# tarocco.net
KiCad netlist of a schematic drawn in EAGLE
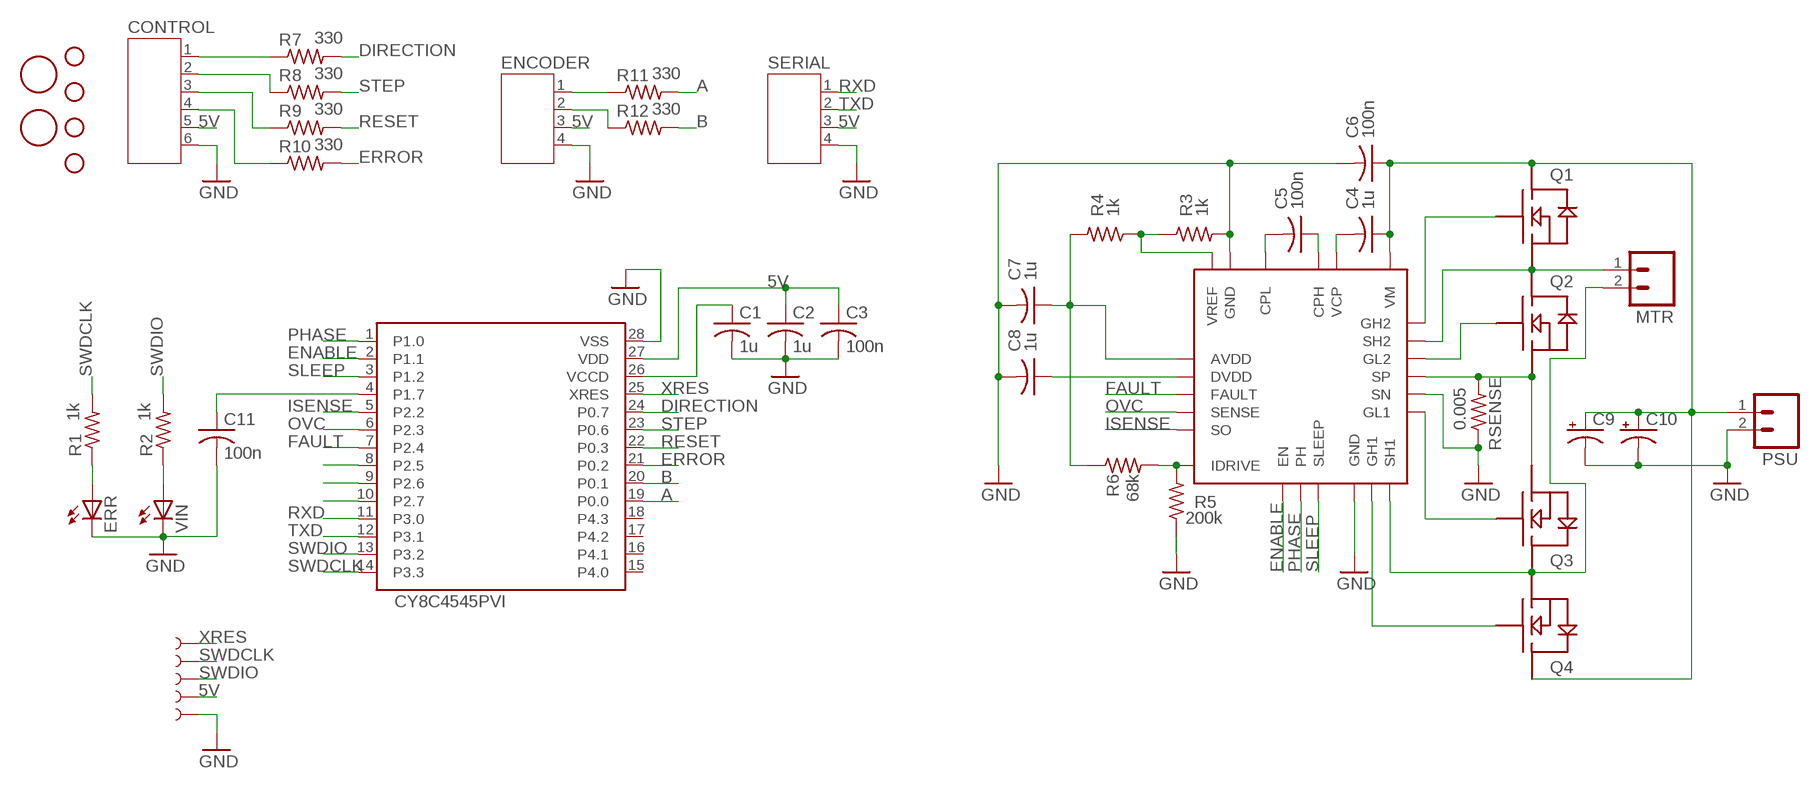
[diagram p0: schematic, sheet 1]

(export (version "E")
  (design (tool "Eeschema 10.0.6"))
  (components
    (comp (ref "8701")
      (value "DRV8701")
      (footprint "eagle-import:VQFN24")
      (libsource (lib "eagle-import") (part "DRV8701"))
    )
    (comp (ref "C1")
      (value "1u")
      (footprint "eagle-import:C0603")
      (libsource (lib "eagle-import") (part "C-USC0603"))
    )
    (comp (ref "C2")
      (value "1u")
      (footprint "eagle-import:C0603")
      (libsource (lib "eagle-import") (part "C-USC0603"))
    )
    (comp (ref "C3")
      (value "100n")
      (footprint "eagle-import:C0603")
      (libsource (lib "eagle-import") (part "C-USC0603"))
    )
    (comp (ref "C4")
      (value "1u")
      (footprint "eagle-import:C0603")
      (libsource (lib "eagle-import") (part "C-USC0603"))
    )
    (comp (ref "C5")
      (value "100n")
      (footprint "eagle-import:C0603")
      (libsource (lib "eagle-import") (part "C-USC0603"))
    )
    (comp (ref "C6")
      (value "100n")
      (footprint "eagle-import:C0603")
      (libsource (lib "eagle-import") (part "C-USC0603"))
    )
    (comp (ref "C7")
      (value "1u")
      (footprint "eagle-import:C0603")
      (libsource (lib "eagle-import") (part "C-USC0603"))
    )
    (comp (ref "C8")
      (value "1u")
      (footprint "eagle-import:C0603")
      (libsource (lib "eagle-import") (part "C-USC0603"))
    )
    (comp (ref "C9")
      (value "CPOL-USE3.5-8")
      (footprint "eagle-import:E3,5-8")
      (libsource (lib "eagle-import") (part "CPOL-USE3.5-8"))
    )
    (comp (ref "C10")
      (value "CPOL-USE3.5-8")
      (footprint "eagle-import:E3,5-8")
      (libsource (lib "eagle-import") (part "CPOL-USE3.5-8"))
    )
    (comp (ref "C11")
      (value "100n")
      (footprint "eagle-import:C0603")
      (libsource (lib "eagle-import") (part "C-USC0603"))
    )
    (comp (ref "CONTROL")
      (value "JST-PH6")
      (footprint "eagle-import:JST-PH6")
      (libsource (lib "eagle-import") (part "JST-PH6"))
    )
    (comp (ref "ENCODER")
      (value "JST-PH4")
      (footprint "eagle-import:JST-PH4")
      (libsource (lib "eagle-import") (part "JST-PH4"))
    )
    (comp (ref "ERR")
      (value "LEDCHIP-LED0603")
      (footprint "eagle-import:CHIP-LED0603")
      (libsource (lib "eagle-import") (part "LEDCHIP-LED0603"))
    )
    (comp (ref "IC1")
      (value "CY8C4545PVI")
      (footprint "eagle-import:SSOP28")
      (libsource (lib "eagle-import") (part "CY8C4545PVI"))
    )
    (comp (ref "MTR")
      (value "M023.5MM")
      (footprint "eagle-import:SCREWTERMINAL-3.5MM-2")
      (libsource (lib "eagle-import") (part "M023.5MM"))
    )
    (comp (ref "PSU")
      (value "M023.5MM")
      (footprint "eagle-import:SCREWTERMINAL-3.5MM-2")
      (libsource (lib "eagle-import") (part "M023.5MM"))
    )
    (comp (ref "Q1")
      (value "NEXFET_SINGLECSD18537NQ5A")
      (footprint "eagle-import:SON5X6")
      (libsource (lib "eagle-import") (part "NEXFET_SINGLECSD18537NQ5A"))
    )
    (comp (ref "Q2")
      (value "NEXFET_SINGLECSD18537NQ5A")
      (footprint "eagle-import:SON5X6")
      (libsource (lib "eagle-import") (part "NEXFET_SINGLECSD18537NQ5A"))
    )
    (comp (ref "Q3")
      (value "NEXFET_SINGLECSD18537NQ5A")
      (footprint "eagle-import:SON5X6")
      (libsource (lib "eagle-import") (part "NEXFET_SINGLECSD18537NQ5A"))
    )
    (comp (ref "Q4")
      (value "NEXFET_SINGLECSD18537NQ5A")
      (footprint "eagle-import:SON5X6")
      (libsource (lib "eagle-import") (part "NEXFET_SINGLECSD18537NQ5A"))
    )
    (comp (ref "R1")
      (value "1k")
      (footprint "eagle-import:R0603")
      (libsource (lib "eagle-import") (part "R-US_R0603"))
    )
    (comp (ref "R2")
      (value "1k")
      (footprint "eagle-import:R0603")
      (libsource (lib "eagle-import") (part "R-US_R0603"))
    )
    (comp (ref "R3")
      (value "1k")
      (footprint "eagle-import:R0603")
      (libsource (lib "eagle-import") (part "R-US_R0603"))
    )
    (comp (ref "R4")
      (value "1k")
      (footprint "eagle-import:R0603")
      (libsource (lib "eagle-import") (part "R-US_R0603"))
    )
    (comp (ref "R5")
      (value "200k")
      (footprint "eagle-import:R0603")
      (libsource (lib "eagle-import") (part "R-US_R0603"))
    )
    (comp (ref "R6")
      (value "68k")
      (footprint "eagle-import:R0603")
      (libsource (lib "eagle-import") (part "R-US_R0603"))
    )
    (comp (ref "R7")
      (value "330")
      (footprint "eagle-import:R0603")
      (libsource (lib "eagle-import") (part "R-US_R0603"))
    )
    (comp (ref "R8")
      (value "330")
      (footprint "eagle-import:R0603")
      (libsource (lib "eagle-import") (part "R-US_R0603"))
    )
    (comp (ref "R9")
      (value "330")
      (footprint "eagle-import:R0603")
      (libsource (lib "eagle-import") (part "R-US_R0603"))
    )
    (comp (ref "R10")
      (value "330")
      (footprint "eagle-import:R0603")
      (libsource (lib "eagle-import") (part "R-US_R0603"))
    )
    (comp (ref "R11")
      (value "330")
      (footprint "eagle-import:R0603")
      (libsource (lib "eagle-import") (part "R-US_R0603"))
    )
    (comp (ref "R12")
      (value "330")
      (footprint "eagle-import:R0603")
      (libsource (lib "eagle-import") (part "R-US_R0603"))
    )
    (comp (ref "RSENSE")
      (value "0.005")
      (footprint "eagle-import:R2512")
      (libsource (lib "eagle-import") (part "R-US_R2512"))
    )
    (comp (ref "SERIAL")
      (value "JST-PH4")
      (footprint "eagle-import:JST-PH4")
      (libsource (lib "eagle-import") (part "JST-PH4"))
    )
    (comp (ref "STANDOFF1")
      (value "STAND-OFF")
      (footprint "eagle-import:STAND-OFF")
      (libsource (lib "eagle-import") (part "STAND-OFF"))
    )
    (comp (ref "STANDOFF2")
      (value "STAND-OFF")
      (footprint "eagle-import:STAND-OFF")
      (libsource (lib "eagle-import") (part "STAND-OFF"))
    )
    (comp (ref "STANDOFF3")
      (value "STAND-OFF")
      (footprint "eagle-import:STAND-OFF")
      (libsource (lib "eagle-import") (part "STAND-OFF"))
    )
    (comp (ref "STANDOFF4")
      (value "STAND-OFF")
      (footprint "eagle-import:STAND-OFF")
      (libsource (lib "eagle-import") (part "STAND-OFF"))
    )
    (comp (ref "TP1")
      (value "TEST-POINT3X5")
      (footprint "eagle-import:PAD.03X.05")
      (libsource (lib "eagle-import") (part "TEST-POINT3X5"))
    )
    (comp (ref "TP2")
      (value "TEST-POINT3X5")
      (footprint "eagle-import:PAD.03X.05")
      (libsource (lib "eagle-import") (part "TEST-POINT3X5"))
    )
    (comp (ref "TP3")
      (value "TEST-POINT3X5")
      (footprint "eagle-import:PAD.03X.05")
      (libsource (lib "eagle-import") (part "TEST-POINT3X5"))
    )
    (comp (ref "TP4")
      (value "TEST-POINT3X5")
      (footprint "eagle-import:PAD.03X.05")
      (libsource (lib "eagle-import") (part "TEST-POINT3X5"))
    )
    (comp (ref "TP5")
      (value "TEST-POINT3X5")
      (footprint "eagle-import:PAD.03X.05")
      (libsource (lib "eagle-import") (part "TEST-POINT3X5"))
    )
    (comp (ref "U$1")
      (value "FIDUCIAL")
      (footprint "eagle-import:FIDUCIAL_1MM")
      (libsource (lib "eagle-import") (part "FIDUCIAL"))
    )
    (comp (ref "U$3")
      (value "FIDUCIAL")
      (footprint "eagle-import:FIDUCIAL_1MM")
      (libsource (lib "eagle-import") (part "FIDUCIAL"))
    )
    (comp (ref "VIN")
      (value "LEDCHIP-LED0603")
      (footprint "eagle-import:CHIP-LED0603")
      (libsource (lib "eagle-import") (part "LEDCHIP-LED0603"))
    )
  )
  (nets
    (net (code "1") (name "/5V") (class "Default")
      (node (ref "C2") (pin "1") (pinfunction "1_1") (pintype "passive"))
      (node (ref "C3") (pin "1") (pinfunction "1_1") (pintype "passive"))
      (node (ref "CONTROL") (pin "5") (pinfunction "5_5") (pintype "passive"))
      (node (ref "ENCODER") (pin "3") (pinfunction "3_3") (pintype "passive"))
      (node (ref "IC1") (pin "27") (pinfunction "VDD_27") (pintype "power_in"))
      (node (ref "SERIAL") (pin "3") (pinfunction "3_3") (pintype "passive"))
      (node (ref "TP4") (pin "P$1") (pinfunction "1_P$1") (pintype "bidirectional"))
    )
    (net (code "2") (name "/A") (class "Default")
      (node (ref "IC1") (pin "19") (pinfunction "P0.0_19") (pintype "bidirectional"))
      (node (ref "R11") (pin "2") (pinfunction "2_2") (pintype "passive"))
    )
    (net (code "3") (name "/B") (class "Default")
      (node (ref "IC1") (pin "20") (pinfunction "P0.1_20") (pintype "bidirectional"))
      (node (ref "R12") (pin "2") (pinfunction "2_2") (pintype "passive"))
    )
    (net (code "4") (name "/DIRECTION") (class "Default")
      (node (ref "IC1") (pin "24") (pinfunction "P0.7_24") (pintype "bidirectional"))
      (node (ref "R7") (pin "2") (pinfunction "2_2") (pintype "passive"))
    )
    (net (code "5") (name "/ENABLE") (class "Default")
      (node (ref "8701") (pin "EN") (pinfunction "EN_EN") (pintype "bidirectional"))
      (node (ref "IC1") (pin "2") (pinfunction "P1.1_2") (pintype "bidirectional"))
    )
    (net (code "6") (name "/ERROR") (class "Default")
      (node (ref "IC1") (pin "21") (pinfunction "P0.2_21") (pintype "bidirectional"))
      (node (ref "R10") (pin "2") (pinfunction "2_2") (pintype "passive"))
    )
    (net (code "7") (name "/FAULT") (class "Default")
      (node (ref "8701") (pin "FAULT") (pinfunction "FAULT_FAULT") (pintype "bidirectional"))
      (node (ref "IC1") (pin "7") (pinfunction "P2.4_7") (pintype "bidirectional"))
    )
    (net (code "8") (name "/ISENSE") (class "Default")
      (node (ref "8701") (pin "SO") (pinfunction "SO_SO") (pintype "bidirectional"))
      (node (ref "IC1") (pin "5") (pinfunction "P2.2_5") (pintype "bidirectional"))
    )
    (net (code "9") (name "/OVC") (class "Default")
      (node (ref "8701") (pin "SENSE") (pinfunction "SENSE_SENSE") (pintype "bidirectional"))
      (node (ref "IC1") (pin "6") (pinfunction "P2.3_6") (pintype "bidirectional"))
    )
    (net (code "10") (name "/PHASE") (class "Default")
      (node (ref "8701") (pin "PH") (pinfunction "PH_PH") (pintype "bidirectional"))
      (node (ref "IC1") (pin "1") (pinfunction "P1.0_1") (pintype "bidirectional"))
    )
    (net (code "11") (name "/RESET") (class "Default")
      (node (ref "IC1") (pin "22") (pinfunction "P0.3_22") (pintype "bidirectional"))
      (node (ref "R9") (pin "2") (pinfunction "2_2") (pintype "passive"))
    )
    (net (code "12") (name "/RXD") (class "Default")
      (node (ref "IC1") (pin "11") (pinfunction "P3.0_11") (pintype "bidirectional"))
      (node (ref "SERIAL") (pin "1") (pinfunction "1_1") (pintype "passive"))
    )
    (net (code "13") (name "/SLEEP") (class "Default")
      (node (ref "8701") (pin "SLEEP") (pinfunction "SLEEP_SLEEP") (pintype "bidirectional"))
      (node (ref "IC1") (pin "3") (pinfunction "P1.2_3") (pintype "bidirectional"))
    )
    (net (code "14") (name "/STEP") (class "Default")
      (node (ref "IC1") (pin "23") (pinfunction "P0.6_23") (pintype "bidirectional"))
      (node (ref "R8") (pin "2") (pinfunction "2_2") (pintype "passive"))
    )
    (net (code "15") (name "/SWDCLK") (class "Default")
      (node (ref "IC1") (pin "14") (pinfunction "P3.3_14") (pintype "bidirectional"))
      (node (ref "R1") (pin "2") (pinfunction "2_2") (pintype "passive"))
      (node (ref "TP2") (pin "P$1") (pinfunction "1_P$1") (pintype "bidirectional"))
    )
    (net (code "16") (name "/SWDIO") (class "Default")
      (node (ref "IC1") (pin "13") (pinfunction "P3.2_13") (pintype "bidirectional"))
      (node (ref "R2") (pin "2") (pinfunction "2_2") (pintype "passive"))
      (node (ref "TP3") (pin "P$1") (pinfunction "1_P$1") (pintype "bidirectional"))
    )
    (net (code "17") (name "/TXD") (class "Default")
      (node (ref "IC1") (pin "12") (pinfunction "P3.1_12") (pintype "bidirectional"))
      (node (ref "SERIAL") (pin "2") (pinfunction "2_2") (pintype "passive"))
    )
    (net (code "18") (name "/XRES") (class "Default")
      (node (ref "IC1") (pin "25") (pinfunction "XRES_25") (pintype "bidirectional"))
      (node (ref "TP1") (pin "P$1") (pinfunction "1_P$1") (pintype "bidirectional"))
    )
    (net (code "19") (name "GND") (class "Default")
      (node (ref "8701") (pin "GND@1") (pinfunction "GND_GND@1") (pintype "bidirectional"))
      (node (ref "8701") (pin "GND@2") (pinfunction "GND_GND@2") (pintype "bidirectional"))
      (node (ref "8701") (pin "GND@3") (pinfunction "GND_GND@3") (pintype "bidirectional"))
      (node (ref "8701") (pin "SN") (pinfunction "SN_SN") (pintype "bidirectional"))
      (node (ref "C1") (pin "2") (pinfunction "2_2") (pintype "passive"))
      (node (ref "C10") (pin "-") (pinfunction "-_-") (pintype "passive"))
      (node (ref "C11") (pin "2") (pinfunction "2_2") (pintype "passive"))
      (node (ref "C2") (pin "2") (pinfunction "2_2") (pintype "passive"))
      (node (ref "C3") (pin "2") (pinfunction "2_2") (pintype "passive"))
      (node (ref "C6") (pin "2") (pinfunction "2_2") (pintype "passive"))
      (node (ref "C7") (pin "2") (pinfunction "2_2") (pintype "passive"))
      (node (ref "C8") (pin "2") (pinfunction "2_2") (pintype "passive"))
      (node (ref "C9") (pin "-") (pinfunction "-_-") (pintype "passive"))
      (node (ref "CONTROL") (pin "6") (pinfunction "6_6") (pintype "passive"))
      (node (ref "ENCODER") (pin "4") (pinfunction "4_4") (pintype "passive"))
      (node (ref "ERR") (pin "C") (pinfunction "C_C") (pintype "passive"))
      (node (ref "IC1") (pin "28") (pinfunction "VSS_28") (pintype "power_in"))
      (node (ref "PSU") (pin "2") (pinfunction "2_2") (pintype "passive"))
      (node (ref "R3") (pin "2") (pinfunction "2_2") (pintype "passive"))
      (node (ref "R5") (pin "1") (pinfunction "1_1") (pintype "passive"))
      (node (ref "RSENSE") (pin "1") (pinfunction "1_1") (pintype "passive"))
      (node (ref "SERIAL") (pin "4") (pinfunction "4_4") (pintype "passive"))
      (node (ref "TP5") (pin "P$1") (pinfunction "1_P$1") (pintype "bidirectional"))
      (node (ref "VIN") (pin "C") (pinfunction "C_C") (pintype "passive"))
    )
    (net (code "20") (name "Net-(8701-PadAVDD)") (class "Default")
      (node (ref "8701") (pin "AVDD") (pinfunction "AVDD_AVDD") (pintype "bidirectional"))
      (node (ref "C7") (pin "1") (pinfunction "1_1") (pintype "passive"))
      (node (ref "R4") (pin "2") (pinfunction "2_2") (pintype "passive"))
      (node (ref "R6") (pin "1") (pinfunction "1_1") (pintype "passive"))
    )
    (net (code "21") (name "Net-(8701-PadCPH)") (class "Default")
      (node (ref "8701") (pin "CPH") (pinfunction "CPH_CPH") (pintype "bidirectional"))
      (node (ref "C5") (pin "1") (pinfunction "1_1") (pintype "passive"))
    )
    (net (code "22") (name "Net-(8701-PadCPL)") (class "Default")
      (node (ref "8701") (pin "CPL") (pinfunction "CPL_CPL") (pintype "bidirectional"))
      (node (ref "C5") (pin "2") (pinfunction "2_2") (pintype "passive"))
    )
    (net (code "23") (name "Net-(8701-PadDVDD)") (class "Default")
      (node (ref "8701") (pin "DVDD") (pinfunction "DVDD_DVDD") (pintype "bidirectional"))
      (node (ref "C8") (pin "1") (pinfunction "1_1") (pintype "passive"))
    )
    (net (code "24") (name "Net-(8701-PadGH1)") (class "Default")
      (node (ref "8701") (pin "GH1") (pinfunction "GH1_GH1") (pintype "bidirectional"))
      (node (ref "Q4") (pin "GATE") (pinfunction "GATE_GATE") (pintype "bidirectional"))
    )
    (net (code "25") (name "Net-(8701-PadGH2)") (class "Default")
      (node (ref "8701") (pin "GH2") (pinfunction "GH2_GH2") (pintype "bidirectional"))
      (node (ref "Q1") (pin "GATE") (pinfunction "GATE_GATE") (pintype "bidirectional"))
    )
    (net (code "26") (name "Net-(8701-PadGL1)") (class "Default")
      (node (ref "8701") (pin "GL1") (pinfunction "GL1_GL1") (pintype "bidirectional"))
      (node (ref "Q3") (pin "GATE") (pinfunction "GATE_GATE") (pintype "bidirectional"))
    )
    (net (code "27") (name "Net-(8701-PadGL2)") (class "Default")
      (node (ref "8701") (pin "GL2") (pinfunction "GL2_GL2") (pintype "bidirectional"))
      (node (ref "Q2") (pin "GATE") (pinfunction "GATE_GATE") (pintype "bidirectional"))
    )
    (net (code "28") (name "Net-(8701-PadIDRIVE)") (class "Default")
      (node (ref "8701") (pin "IDRIVE") (pinfunction "IDRIVE_IDRIVE") (pintype "bidirectional"))
      (node (ref "R5") (pin "2") (pinfunction "2_2") (pintype "passive"))
      (node (ref "R6") (pin "2") (pinfunction "2_2") (pintype "passive"))
    )
    (net (code "29") (name "Net-(8701-PadSH1)") (class "Default")
      (node (ref "8701") (pin "SH1") (pinfunction "SH1_SH1") (pintype "bidirectional"))
      (node (ref "MTR") (pin "2") (pinfunction "2_2") (pintype "passive"))
      (node (ref "Q3") (pin "DRAIN@1") (pinfunction "DRAIN_DRAIN@1") (pintype "bidirectional"))
      (node (ref "Q3") (pin "DRAIN@2") (pinfunction "DRAIN_DRAIN@2") (pintype "bidirectional"))
      (node (ref "Q3") (pin "DRAIN@3") (pinfunction "DRAIN_DRAIN@3") (pintype "bidirectional"))
      (node (ref "Q3") (pin "DRAIN@4") (pinfunction "DRAIN_DRAIN@4") (pintype "bidirectional"))
      (node (ref "Q3") (pin "DRAIN@5") (pinfunction "DRAIN_DRAIN@5") (pintype "bidirectional"))
      (node (ref "Q4") (pin "SOURCE@1") (pinfunction "SOURCE_SOURCE@1") (pintype "bidirectional"))
      (node (ref "Q4") (pin "SOURCE@2") (pinfunction "SOURCE_SOURCE@2") (pintype "bidirectional"))
      (node (ref "Q4") (pin "SOURCE@3") (pinfunction "SOURCE_SOURCE@3") (pintype "bidirectional"))
    )
    (net (code "30") (name "Net-(8701-PadSH2)") (class "Default")
      (node (ref "8701") (pin "SH2") (pinfunction "SH2_SH2") (pintype "bidirectional"))
      (node (ref "MTR") (pin "1") (pinfunction "1_1") (pintype "passive"))
      (node (ref "Q1") (pin "SOURCE@1") (pinfunction "SOURCE_SOURCE@1") (pintype "bidirectional"))
      (node (ref "Q1") (pin "SOURCE@2") (pinfunction "SOURCE_SOURCE@2") (pintype "bidirectional"))
      (node (ref "Q1") (pin "SOURCE@3") (pinfunction "SOURCE_SOURCE@3") (pintype "bidirectional"))
      (node (ref "Q2") (pin "DRAIN@1") (pinfunction "DRAIN_DRAIN@1") (pintype "bidirectional"))
      (node (ref "Q2") (pin "DRAIN@2") (pinfunction "DRAIN_DRAIN@2") (pintype "bidirectional"))
      (node (ref "Q2") (pin "DRAIN@3") (pinfunction "DRAIN_DRAIN@3") (pintype "bidirectional"))
      (node (ref "Q2") (pin "DRAIN@4") (pinfunction "DRAIN_DRAIN@4") (pintype "bidirectional"))
      (node (ref "Q2") (pin "DRAIN@5") (pinfunction "DRAIN_DRAIN@5") (pintype "bidirectional"))
    )
    (net (code "31") (name "Net-(8701-PadSP)") (class "Default")
      (node (ref "8701") (pin "SP") (pinfunction "SP_SP") (pintype "bidirectional"))
      (node (ref "Q2") (pin "SOURCE@1") (pinfunction "SOURCE_SOURCE@1") (pintype "bidirectional"))
      (node (ref "Q2") (pin "SOURCE@2") (pinfunction "SOURCE_SOURCE@2") (pintype "bidirectional"))
      (node (ref "Q2") (pin "SOURCE@3") (pinfunction "SOURCE_SOURCE@3") (pintype "bidirectional"))
      (node (ref "Q3") (pin "SOURCE@1") (pinfunction "SOURCE_SOURCE@1") (pintype "bidirectional"))
      (node (ref "Q3") (pin "SOURCE@2") (pinfunction "SOURCE_SOURCE@2") (pintype "bidirectional"))
      (node (ref "Q3") (pin "SOURCE@3") (pinfunction "SOURCE_SOURCE@3") (pintype "bidirectional"))
      (node (ref "RSENSE") (pin "2") (pinfunction "2_2") (pintype "passive"))
    )
    (net (code "32") (name "Net-(8701-PadVCP)") (class "Default")
      (node (ref "8701") (pin "VCP") (pinfunction "VCP_VCP") (pintype "bidirectional"))
      (node (ref "C4") (pin "2") (pinfunction "2_2") (pintype "passive"))
    )
    (net (code "33") (name "Net-(8701-PadVM)") (class "Default")
      (node (ref "8701") (pin "VM") (pinfunction "VM_VM") (pintype "bidirectional"))
      (node (ref "C10") (pin "+") (pinfunction "+_+") (pintype "passive"))
      (node (ref "C4") (pin "1") (pinfunction "1_1") (pintype "passive"))
      (node (ref "C6") (pin "1") (pinfunction "1_1") (pintype "passive"))
      (node (ref "C9") (pin "+") (pinfunction "+_+") (pintype "passive"))
      (node (ref "PSU") (pin "1") (pinfunction "1_1") (pintype "passive"))
      (node (ref "Q1") (pin "DRAIN@1") (pinfunction "DRAIN_DRAIN@1") (pintype "bidirectional"))
      (node (ref "Q1") (pin "DRAIN@2") (pinfunction "DRAIN_DRAIN@2") (pintype "bidirectional"))
      (node (ref "Q1") (pin "DRAIN@3") (pinfunction "DRAIN_DRAIN@3") (pintype "bidirectional"))
      (node (ref "Q1") (pin "DRAIN@4") (pinfunction "DRAIN_DRAIN@4") (pintype "bidirectional"))
      (node (ref "Q1") (pin "DRAIN@5") (pinfunction "DRAIN_DRAIN@5") (pintype "bidirectional"))
      (node (ref "Q4") (pin "DRAIN@1") (pinfunction "DRAIN_DRAIN@1") (pintype "bidirectional"))
      (node (ref "Q4") (pin "DRAIN@2") (pinfunction "DRAIN_DRAIN@2") (pintype "bidirectional"))
      (node (ref "Q4") (pin "DRAIN@3") (pinfunction "DRAIN_DRAIN@3") (pintype "bidirectional"))
      (node (ref "Q4") (pin "DRAIN@4") (pinfunction "DRAIN_DRAIN@4") (pintype "bidirectional"))
      (node (ref "Q4") (pin "DRAIN@5") (pinfunction "DRAIN_DRAIN@5") (pintype "bidirectional"))
    )
    (net (code "34") (name "Net-(8701-PadVREF)") (class "Default")
      (node (ref "8701") (pin "VREF") (pinfunction "VREF_VREF") (pintype "bidirectional"))
      (node (ref "R3") (pin "1") (pinfunction "1_1") (pintype "passive"))
      (node (ref "R4") (pin "1") (pinfunction "1_1") (pintype "passive"))
    )
    (net (code "35") (name "Net-(CONTROL-Pad1)") (class "Default")
      (node (ref "CONTROL") (pin "1") (pinfunction "1_1") (pintype "passive"))
      (node (ref "R7") (pin "1") (pinfunction "1_1") (pintype "passive"))
    )
    (net (code "36") (name "Net-(CONTROL-Pad2)") (class "Default")
      (node (ref "CONTROL") (pin "2") (pinfunction "2_2") (pintype "passive"))
      (node (ref "R8") (pin "1") (pinfunction "1_1") (pintype "passive"))
    )
    (net (code "37") (name "Net-(CONTROL-Pad3)") (class "Default")
      (node (ref "CONTROL") (pin "3") (pinfunction "3_3") (pintype "passive"))
      (node (ref "R9") (pin "1") (pinfunction "1_1") (pintype "passive"))
    )
    (net (code "38") (name "Net-(CONTROL-Pad4)") (class "Default")
      (node (ref "CONTROL") (pin "4") (pinfunction "4_4") (pintype "passive"))
      (node (ref "R10") (pin "1") (pinfunction "1_1") (pintype "passive"))
    )
    (net (code "39") (name "Net-(ENCODER-Pad1)") (class "Default")
      (node (ref "ENCODER") (pin "1") (pinfunction "1_1") (pintype "passive"))
      (node (ref "R11") (pin "1") (pinfunction "1_1") (pintype "passive"))
    )
    (net (code "40") (name "Net-(ENCODER-Pad2)") (class "Default")
      (node (ref "ENCODER") (pin "2") (pinfunction "2_2") (pintype "passive"))
      (node (ref "R12") (pin "1") (pinfunction "1_1") (pintype "passive"))
    )
    (net (code "41") (name "Net-(ERR-PadA)") (class "Default")
      (node (ref "ERR") (pin "A") (pinfunction "A_A") (pintype "passive"))
      (node (ref "R1") (pin "1") (pinfunction "1_1") (pintype "passive"))
    )
    (net (code "42") (name "Net-(IC1-P1.7)") (class "Default")
      (node (ref "C11") (pin "1") (pinfunction "1_1") (pintype "passive"))
      (node (ref "IC1") (pin "4") (pinfunction "P1.7_4") (pintype "bidirectional"))
    )
    (net (code "43") (name "Net-(IC1-VCCD)") (class "Default")
      (node (ref "C1") (pin "1") (pinfunction "1_1") (pintype "passive"))
      (node (ref "IC1") (pin "26") (pinfunction "VCCD_26") (pintype "power_in"))
    )
    (net (code "44") (name "Net-(R2-Pad1)") (class "Default")
      (node (ref "R2") (pin "1") (pinfunction "1_1") (pintype "passive"))
      (node (ref "VIN") (pin "A") (pinfunction "A_A") (pintype "passive"))
    )
    (net (code "45") (name "unconnected-(IC1-P2.5-Pad8)") (class "Default")
      (node (ref "IC1") (pin "8") (pinfunction "P2.5_8") (pintype "bidirectional"))
    )
    (net (code "46") (name "unconnected-(IC1-P2.6-Pad9)") (class "Default")
      (node (ref "IC1") (pin "9") (pinfunction "P2.6_9") (pintype "bidirectional"))
    )
    (net (code "47") (name "unconnected-(IC1-P2.7-Pad10)") (class "Default")
      (node (ref "IC1") (pin "10") (pinfunction "P2.7_10") (pintype "bidirectional"))
    )
    (net (code "48") (name "unconnected-(IC1-P4.0-Pad15)") (class "Default")
      (node (ref "IC1") (pin "15") (pinfunction "P4.0_15") (pintype "bidirectional"))
    )
    (net (code "49") (name "unconnected-(IC1-P4.1-Pad16)") (class "Default")
      (node (ref "IC1") (pin "16") (pinfunction "P4.1_16") (pintype "bidirectional"))
    )
    (net (code "50") (name "unconnected-(IC1-P4.2-Pad17)") (class "Default")
      (node (ref "IC1") (pin "17") (pinfunction "P4.2_17") (pintype "bidirectional"))
    )
    (net (code "51") (name "unconnected-(IC1-P4.3-Pad18)") (class "Default")
      (node (ref "IC1") (pin "18") (pinfunction "P4.3_18") (pintype "bidirectional"))
    )
  )
)
